# Current_Limit.net
KiCad netlist of a schematic drawn in Altium Designer
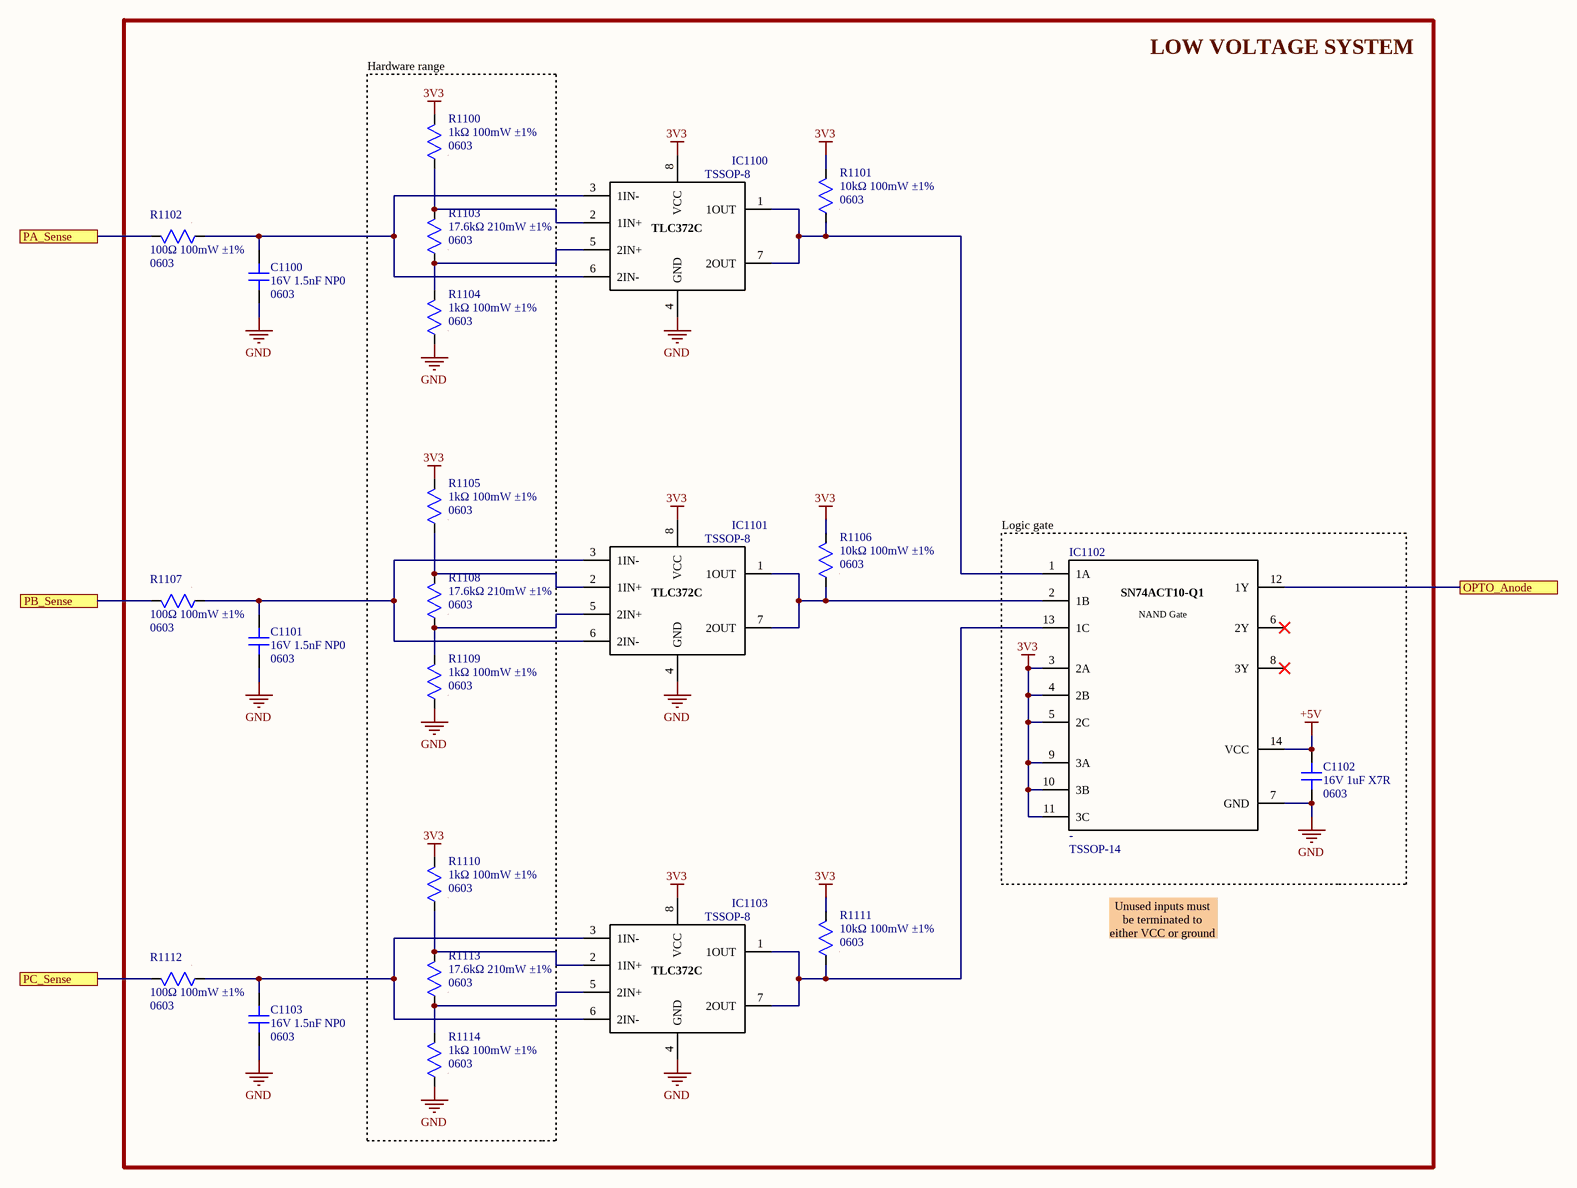
[diagram p0: Current_Limit.SchDoc]

(export (version "E")
  (design (tool "Eeschema 10.0.6"))
  (components
    (comp (ref "C1100")
      (value "16V 1.5nF NP0")
      (footprint "CAP SMD 0603")
      (description "Condensadores de cerámica multicapa (MLCC- SMD/SMT) 25V 1500pF C0G 0603 1%")
      (fields
        (field (name "PACKAGE") "0603")
        (field (name "MPN") "C0603C152F3GECTU")
        (field (name "MANUFACTURER") "KEMET")
      )
      (libsource (lib "eUSR_Database") (part "CAP non polarized"))
    )
    (comp (ref "C1101")
      (value "16V 1.5nF NP0")
      (footprint "CAP SMD 0603")
      (description "Condensadores de cerámica multicapa (MLCC- SMD/SMT) 25V 1500pF C0G 0603 1%")
      (fields
        (field (name "PACKAGE") "0603")
        (field (name "MPN") "C0603C152F3GECTU")
        (field (name "MANUFACTURER") "KEMET")
      )
      (libsource (lib "eUSR_Database") (part "CAP non polarized"))
    )
    (comp (ref "C1102")
      (value "16V 1uF X7R")
      (footprint "CAP SMD 0603")
      (description "Condensadores de cerámica multicapa (MLCC- SMD/SMT) WCAP-CSGP 1uF 0603 10% 16V MLCC")
      (fields
        (field (name "PACKAGE") "0603")
        (field (name "MPN") "885012206052")
        (field (name "MANUFACTURER") "Wurth Elektronik")
      )
      (libsource (lib "eUSR_Database") (part "CAP non polarized"))
    )
    (comp (ref "C1103")
      (value "16V 1.5nF NP0")
      (footprint "CAP SMD 0603")
      (description "Condensadores de cerámica multicapa (MLCC- SMD/SMT) 25V 1500pF C0G 0603 1%")
      (fields
        (field (name "PACKAGE") "0603")
        (field (name "MPN") "C0603C152F3GECTU")
        (field (name "MANUFACTURER") "KEMET")
      )
      (libsource (lib "eUSR_Database") (part "CAP non polarized"))
    )
    (comp (ref "IC1100")
      (value "TLC372C")
      (footprint "TSSOP-8")
      (description "Comparadores analógicos Dual Differential A 595-TLC372CPW A 595- A 595-TLC372CPW")
      (fields
        (field (name "PACKAGE") "TSSOP-8")
        (field (name "MPN") "TLC372CPWR")
        (field (name "MANUFACTURER") "Texas Instruments")
      )
      (libsource (lib "eUSR_Database") (part "TLC372C"))
    )
    (comp (ref "IC1101")
      (value "TLC372C")
      (footprint "TSSOP-8")
      (description "Comparadores analógicos Dual Differential A 595-TLC372CPW A 595- A 595-TLC372CPW")
      (fields
        (field (name "PACKAGE") "TSSOP-8")
        (field (name "MPN") "TLC372CPWR")
        (field (name "MANUFACTURER") "Texas Instruments")
      )
      (libsource (lib "eUSR_Database") (part "TLC372C"))
    )
    (comp (ref "IC1102")
      (value "-")
      (footprint "TSSOP-14")
      (description "Puertas lógicas Automotive 3-ch 3- i nput 1.5V to 6V 24")
      (fields
        (field (name "PACKAGE") "TSSOP-14")
        (field (name "MPN") "SN74ACT10QPWRG4Q1")
        (field (name "MANUFACTURER") "Texas Instruments")
      )
      (libsource (lib "eUSR_Database") (part "SN74ACT10-Q1"))
    )
    (comp (ref "IC1103")
      (value "TLC372C")
      (footprint "TSSOP-8")
      (description "Comparadores analógicos Dual Differential A 595-TLC372CPW A 595- A 595-TLC372CPW")
      (fields
        (field (name "PACKAGE") "TSSOP-8")
        (field (name "MPN") "TLC372CPWR")
        (field (name "MANUFACTURER") "Texas Instruments")
      )
      (libsource (lib "eUSR_Database") (part "TLC372C"))
    )
    (comp (ref "R1100")
      (value "1kΩ 100mW ±1%")
      (footprint "RES SMD 0603")
      (description "Thick Film Resistors WRIS-RSKS 1 kOhms 1 % 0.1 W 0603 AEC-Q200")
      (fields
        (field (name "PACKAGE") "0603")
        (field (name "MPN") "560112116014")
        (field (name "MANUFACTURER") "Wurth Elektronik")
      )
      (libsource (lib "eUSR_Database") (part "RES"))
    )
    (comp (ref "R1101")
      (value "10kΩ 100mW ±1%")
      (footprint "RES SMD 0603")
      (description "Resistores de película gruesa - SMD WRIS-RSKS 10 kOhms 1 % 0.1 W 0603 AEC-Q200")
      (fields
        (field (name "PACKAGE") "0603")
        (field (name "MPN") "560112116005")
        (field (name "MANUFACTURER") "Wurth Elektronik")
      )
      (libsource (lib "eUSR_Database") (part "RES"))
    )
    (comp (ref "R1102")
      (value "100Ω 100mW ±1%")
      (footprint "RES SMD 0603")
      (description "Thick Film Resistors WRIS-RSKS 100 Ohms 1 % 0.1 W 0603 AEC-Q200")
      (fields
        (field (name "PACKAGE") "0603")
        (field (name "MPN") "560112116009")
        (field (name "MANUFACTURER") "Wurth Elektronik")
      )
      (libsource (lib "eUSR_Database") (part "RES"))
    )
    (comp (ref "R1103")
      (value "17.6kΩ 210mW ±1%")
      (footprint "RES SMD 0603")
      (description "Thin Film Resistors 17.6Kohms .1% 25ppm")
      (fields
        (field (name "PACKAGE") "0603")
        (field (name "MPN") "TNPW060317K6BEEA")
        (field (name "MANUFACTURER") "Vishay")
      )
      (libsource (lib "eUSR_Database") (part "RES"))
    )
    (comp (ref "R1104")
      (value "1kΩ 100mW ±1%")
      (footprint "RES SMD 0603")
      (description "Thick Film Resistors WRIS-RSKS 1 kOhms 1 % 0.1 W 0603 AEC-Q200")
      (fields
        (field (name "PACKAGE") "0603")
        (field (name "MPN") "560112116014")
        (field (name "MANUFACTURER") "Wurth Elektronik")
      )
      (libsource (lib "eUSR_Database") (part "RES"))
    )
    (comp (ref "R1105")
      (value "1kΩ 100mW ±1%")
      (footprint "RES SMD 0603")
      (description "Thick Film Resistors WRIS-RSKS 1 kOhms 1 % 0.1 W 0603 AEC-Q200")
      (fields
        (field (name "PACKAGE") "0603")
        (field (name "MPN") "560112116014")
        (field (name "MANUFACTURER") "Wurth Elektronik")
      )
      (libsource (lib "eUSR_Database") (part "RES"))
    )
    (comp (ref "R1106")
      (value "10kΩ 100mW ±1%")
      (footprint "RES SMD 0603")
      (description "Resistores de película gruesa - SMD WRIS-RSKS 10 kOhms 1 % 0.1 W 0603 AEC-Q200")
      (fields
        (field (name "PACKAGE") "0603")
        (field (name "MPN") "560112116005")
        (field (name "MANUFACTURER") "Wurth Elektronik")
      )
      (libsource (lib "eUSR_Database") (part "RES"))
    )
    (comp (ref "R1107")
      (value "100Ω 100mW ±1%")
      (footprint "RES SMD 0603")
      (description "Thick Film Resistors WRIS-RSKS 100 Ohms 1 % 0.1 W 0603 AEC-Q200")
      (fields
        (field (name "PACKAGE") "0603")
        (field (name "MPN") "560112116009")
        (field (name "MANUFACTURER") "Wurth Elektronik")
      )
      (libsource (lib "eUSR_Database") (part "RES"))
    )
    (comp (ref "R1108")
      (value "17.6kΩ 210mW ±1%")
      (footprint "RES SMD 0603")
      (description "Thin Film Resistors 17.6Kohms .1% 25ppm")
      (fields
        (field (name "PACKAGE") "0603")
        (field (name "MPN") "TNPW060317K6BEEA")
        (field (name "MANUFACTURER") "Vishay")
      )
      (libsource (lib "eUSR_Database") (part "RES"))
    )
    (comp (ref "R1109")
      (value "1kΩ 100mW ±1%")
      (footprint "RES SMD 0603")
      (description "Thick Film Resistors WRIS-RSKS 1 kOhms 1 % 0.1 W 0603 AEC-Q200")
      (fields
        (field (name "PACKAGE") "0603")
        (field (name "MPN") "560112116014")
        (field (name "MANUFACTURER") "Wurth Elektronik")
      )
      (libsource (lib "eUSR_Database") (part "RES"))
    )
    (comp (ref "R1110")
      (value "1kΩ 100mW ±1%")
      (footprint "RES SMD 0603")
      (description "Thick Film Resistors WRIS-RSKS 1 kOhms 1 % 0.1 W 0603 AEC-Q200")
      (fields
        (field (name "PACKAGE") "0603")
        (field (name "MPN") "560112116014")
        (field (name "MANUFACTURER") "Wurth Elektronik")
      )
      (libsource (lib "eUSR_Database") (part "RES"))
    )
    (comp (ref "R1111")
      (value "10kΩ 100mW ±1%")
      (footprint "RES SMD 0603")
      (description "Resistores de película gruesa - SMD WRIS-RSKS 10 kOhms 1 % 0.1 W 0603 AEC-Q200")
      (fields
        (field (name "PACKAGE") "0603")
        (field (name "MPN") "560112116005")
        (field (name "MANUFACTURER") "Wurth Elektronik")
      )
      (libsource (lib "eUSR_Database") (part "RES"))
    )
    (comp (ref "R1112")
      (value "100Ω 100mW ±1%")
      (footprint "RES SMD 0603")
      (description "Thick Film Resistors WRIS-RSKS 100 Ohms 1 % 0.1 W 0603 AEC-Q200")
      (fields
        (field (name "PACKAGE") "0603")
        (field (name "MPN") "560112116009")
        (field (name "MANUFACTURER") "Wurth Elektronik")
      )
      (libsource (lib "eUSR_Database") (part "RES"))
    )
    (comp (ref "R1113")
      (value "17.6kΩ 210mW ±1%")
      (footprint "RES SMD 0603")
      (description "Thin Film Resistors 17.6Kohms .1% 25ppm")
      (fields
        (field (name "PACKAGE") "0603")
        (field (name "MPN") "TNPW060317K6BEEA")
        (field (name "MANUFACTURER") "Vishay")
      )
      (libsource (lib "eUSR_Database") (part "RES"))
    )
    (comp (ref "R1114")
      (value "1kΩ 100mW ±1%")
      (footprint "RES SMD 0603")
      (description "Thick Film Resistors WRIS-RSKS 1 kOhms 1 % 0.1 W 0603 AEC-Q200")
      (fields
        (field (name "PACKAGE") "0603")
        (field (name "MPN") "560112116014")
        (field (name "MANUFACTURER") "Wurth Elektronik")
      )
      (libsource (lib "eUSR_Database") (part "RES"))
    )
  )
  (nets
    (net (code "1") (name "+5V") (class "Default")
      (node (ref "C1102") (pin "2") (pinfunction "2_2") (pintype "passive"))
      (node (ref "IC1102") (pin "14") (pinfunction "VCC_14") (pintype "passive"))
    )
    (net (code "2") (name "/OPTO_Anode") (class "Default")
      (node (ref "IC1102") (pin "12") (pinfunction "1Y_12") (pintype "passive"))
    )
    (net (code "3") (name "/PA_Sense") (class "Default")
      (node (ref "R1102") (pin "2") (pinfunction "2_2") (pintype "passive"))
    )
    (net (code "4") (name "/PB_Sense") (class "Default")
      (node (ref "R1107") (pin "2") (pinfunction "2_2") (pintype "passive"))
    )
    (net (code "5") (name "/PC_Sense") (class "Default")
      (node (ref "R1112") (pin "2") (pinfunction "2_2") (pintype "passive"))
    )
    (net (code "6") (name "3V3") (class "Default")
      (node (ref "IC1100") (pin "8") (pinfunction "VCC_8") (pintype "passive"))
      (node (ref "IC1101") (pin "8") (pinfunction "VCC_8") (pintype "passive"))
      (node (ref "IC1102") (pin "10") (pinfunction "3B_10") (pintype "passive"))
      (node (ref "IC1102") (pin "11") (pinfunction "3C_11") (pintype "passive"))
      (node (ref "IC1102") (pin "3") (pinfunction "2A_3") (pintype "passive"))
      (node (ref "IC1102") (pin "4") (pinfunction "2B_4") (pintype "passive"))
      (node (ref "IC1102") (pin "5") (pinfunction "2C_5") (pintype "passive"))
      (node (ref "IC1102") (pin "9") (pinfunction "3A_9") (pintype "passive"))
      (node (ref "IC1103") (pin "8") (pinfunction "VCC_8") (pintype "passive"))
      (node (ref "R1100") (pin "2") (pinfunction "2_2") (pintype "passive"))
      (node (ref "R1101") (pin "2") (pinfunction "2_2") (pintype "passive"))
      (node (ref "R1105") (pin "2") (pinfunction "2_2") (pintype "passive"))
      (node (ref "R1106") (pin "2") (pinfunction "2_2") (pintype "passive"))
      (node (ref "R1110") (pin "2") (pinfunction "2_2") (pintype "passive"))
      (node (ref "R1111") (pin "2") (pinfunction "2_2") (pintype "passive"))
    )
    (net (code "7") (name "GND") (class "Default")
      (node (ref "C1100") (pin "1") (pinfunction "1_1") (pintype "passive"))
      (node (ref "C1101") (pin "1") (pinfunction "1_1") (pintype "passive"))
      (node (ref "C1102") (pin "1") (pinfunction "1_1") (pintype "passive"))
      (node (ref "C1103") (pin "1") (pinfunction "1_1") (pintype "passive"))
      (node (ref "IC1100") (pin "4") (pinfunction "GND_4") (pintype "passive"))
      (node (ref "IC1101") (pin "4") (pinfunction "GND_4") (pintype "passive"))
      (node (ref "IC1102") (pin "7") (pinfunction "GND_7") (pintype "passive"))
      (node (ref "IC1103") (pin "4") (pinfunction "GND_4") (pintype "passive"))
      (node (ref "R1104") (pin "1") (pinfunction "1_1") (pintype "passive"))
      (node (ref "R1109") (pin "1") (pinfunction "1_1") (pintype "passive"))
      (node (ref "R1114") (pin "1") (pinfunction "1_1") (pintype "passive"))
    )
    (net (code "8") (name "Net-(IC1100-1IN+)") (class "Default")
      (node (ref "IC1100") (pin "2") (pinfunction "1IN+_2") (pintype "passive"))
      (node (ref "R1100") (pin "1") (pinfunction "1_1") (pintype "passive"))
      (node (ref "R1103") (pin "2") (pinfunction "2_2") (pintype "passive"))
    )
    (net (code "9") (name "Net-(IC1100-1IN-)") (class "Default")
      (node (ref "C1100") (pin "2") (pinfunction "2_2") (pintype "passive"))
      (node (ref "IC1100") (pin "3") (pinfunction "1IN-_3") (pintype "passive"))
      (node (ref "IC1100") (pin "6") (pinfunction "2IN-_6") (pintype "passive"))
      (node (ref "R1102") (pin "1") (pinfunction "1_1") (pintype "passive"))
    )
    (net (code "10") (name "Net-(IC1100-1OUT)") (class "Default")
      (node (ref "IC1100") (pin "1") (pinfunction "1OUT_1") (pintype "passive"))
      (node (ref "IC1100") (pin "7") (pinfunction "2OUT_7") (pintype "passive"))
      (node (ref "IC1102") (pin "1") (pinfunction "1A_1") (pintype "passive"))
      (node (ref "R1101") (pin "1") (pinfunction "1_1") (pintype "passive"))
    )
    (net (code "11") (name "Net-(IC1100-2IN+)") (class "Default")
      (node (ref "IC1100") (pin "5") (pinfunction "2IN+_5") (pintype "passive"))
      (node (ref "R1103") (pin "1") (pinfunction "1_1") (pintype "passive"))
      (node (ref "R1104") (pin "2") (pinfunction "2_2") (pintype "passive"))
    )
    (net (code "12") (name "Net-(IC1101-1IN+)") (class "Default")
      (node (ref "IC1101") (pin "2") (pinfunction "1IN+_2") (pintype "passive"))
      (node (ref "R1105") (pin "1") (pinfunction "1_1") (pintype "passive"))
      (node (ref "R1108") (pin "2") (pinfunction "2_2") (pintype "passive"))
    )
    (net (code "13") (name "Net-(IC1101-1IN-)") (class "Default")
      (node (ref "C1101") (pin "2") (pinfunction "2_2") (pintype "passive"))
      (node (ref "IC1101") (pin "3") (pinfunction "1IN-_3") (pintype "passive"))
      (node (ref "IC1101") (pin "6") (pinfunction "2IN-_6") (pintype "passive"))
      (node (ref "R1107") (pin "1") (pinfunction "1_1") (pintype "passive"))
    )
    (net (code "14") (name "Net-(IC1101-1OUT)") (class "Default")
      (node (ref "IC1101") (pin "1") (pinfunction "1OUT_1") (pintype "passive"))
      (node (ref "IC1101") (pin "7") (pinfunction "2OUT_7") (pintype "passive"))
      (node (ref "IC1102") (pin "2") (pinfunction "1B_2") (pintype "passive"))
      (node (ref "R1106") (pin "1") (pinfunction "1_1") (pintype "passive"))
    )
    (net (code "15") (name "Net-(IC1101-2IN+)") (class "Default")
      (node (ref "IC1101") (pin "5") (pinfunction "2IN+_5") (pintype "passive"))
      (node (ref "R1108") (pin "1") (pinfunction "1_1") (pintype "passive"))
      (node (ref "R1109") (pin "2") (pinfunction "2_2") (pintype "passive"))
    )
    (net (code "16") (name "Net-(IC1102-1C)") (class "Default")
      (node (ref "IC1102") (pin "13") (pinfunction "1C_13") (pintype "passive"))
      (node (ref "IC1103") (pin "1") (pinfunction "1OUT_1") (pintype "passive"))
      (node (ref "IC1103") (pin "7") (pinfunction "2OUT_7") (pintype "passive"))
      (node (ref "R1111") (pin "1") (pinfunction "1_1") (pintype "passive"))
    )
    (net (code "17") (name "Net-(IC1103-1IN+)") (class "Default")
      (node (ref "IC1103") (pin "2") (pinfunction "1IN+_2") (pintype "passive"))
      (node (ref "R1110") (pin "1") (pinfunction "1_1") (pintype "passive"))
      (node (ref "R1113") (pin "2") (pinfunction "2_2") (pintype "passive"))
    )
    (net (code "18") (name "Net-(IC1103-1IN-)") (class "Default")
      (node (ref "C1103") (pin "2") (pinfunction "2_2") (pintype "passive"))
      (node (ref "IC1103") (pin "3") (pinfunction "1IN-_3") (pintype "passive"))
      (node (ref "IC1103") (pin "6") (pinfunction "2IN-_6") (pintype "passive"))
      (node (ref "R1112") (pin "1") (pinfunction "1_1") (pintype "passive"))
    )
    (net (code "19") (name "Net-(IC1103-2IN+)") (class "Default")
      (node (ref "IC1103") (pin "5") (pinfunction "2IN+_5") (pintype "passive"))
      (node (ref "R1113") (pin "1") (pinfunction "1_1") (pintype "passive"))
      (node (ref "R1114") (pin "2") (pinfunction "2_2") (pintype "passive"))
    )
    (net (code "20") (name "unconnected-(IC1102-2Y-Pad6)") (class "Default")
      (node (ref "IC1102") (pin "6") (pinfunction "2Y_6") (pintype "passive+no_connect"))
    )
    (net (code "21") (name "unconnected-(IC1102-3Y-Pad8)") (class "Default")
      (node (ref "IC1102") (pin "8") (pinfunction "3Y_8") (pintype "passive+no_connect"))
    )
  )
)
